# m301-stereo-output.net
KiCad netlist of a schematic drawn in EAGLE
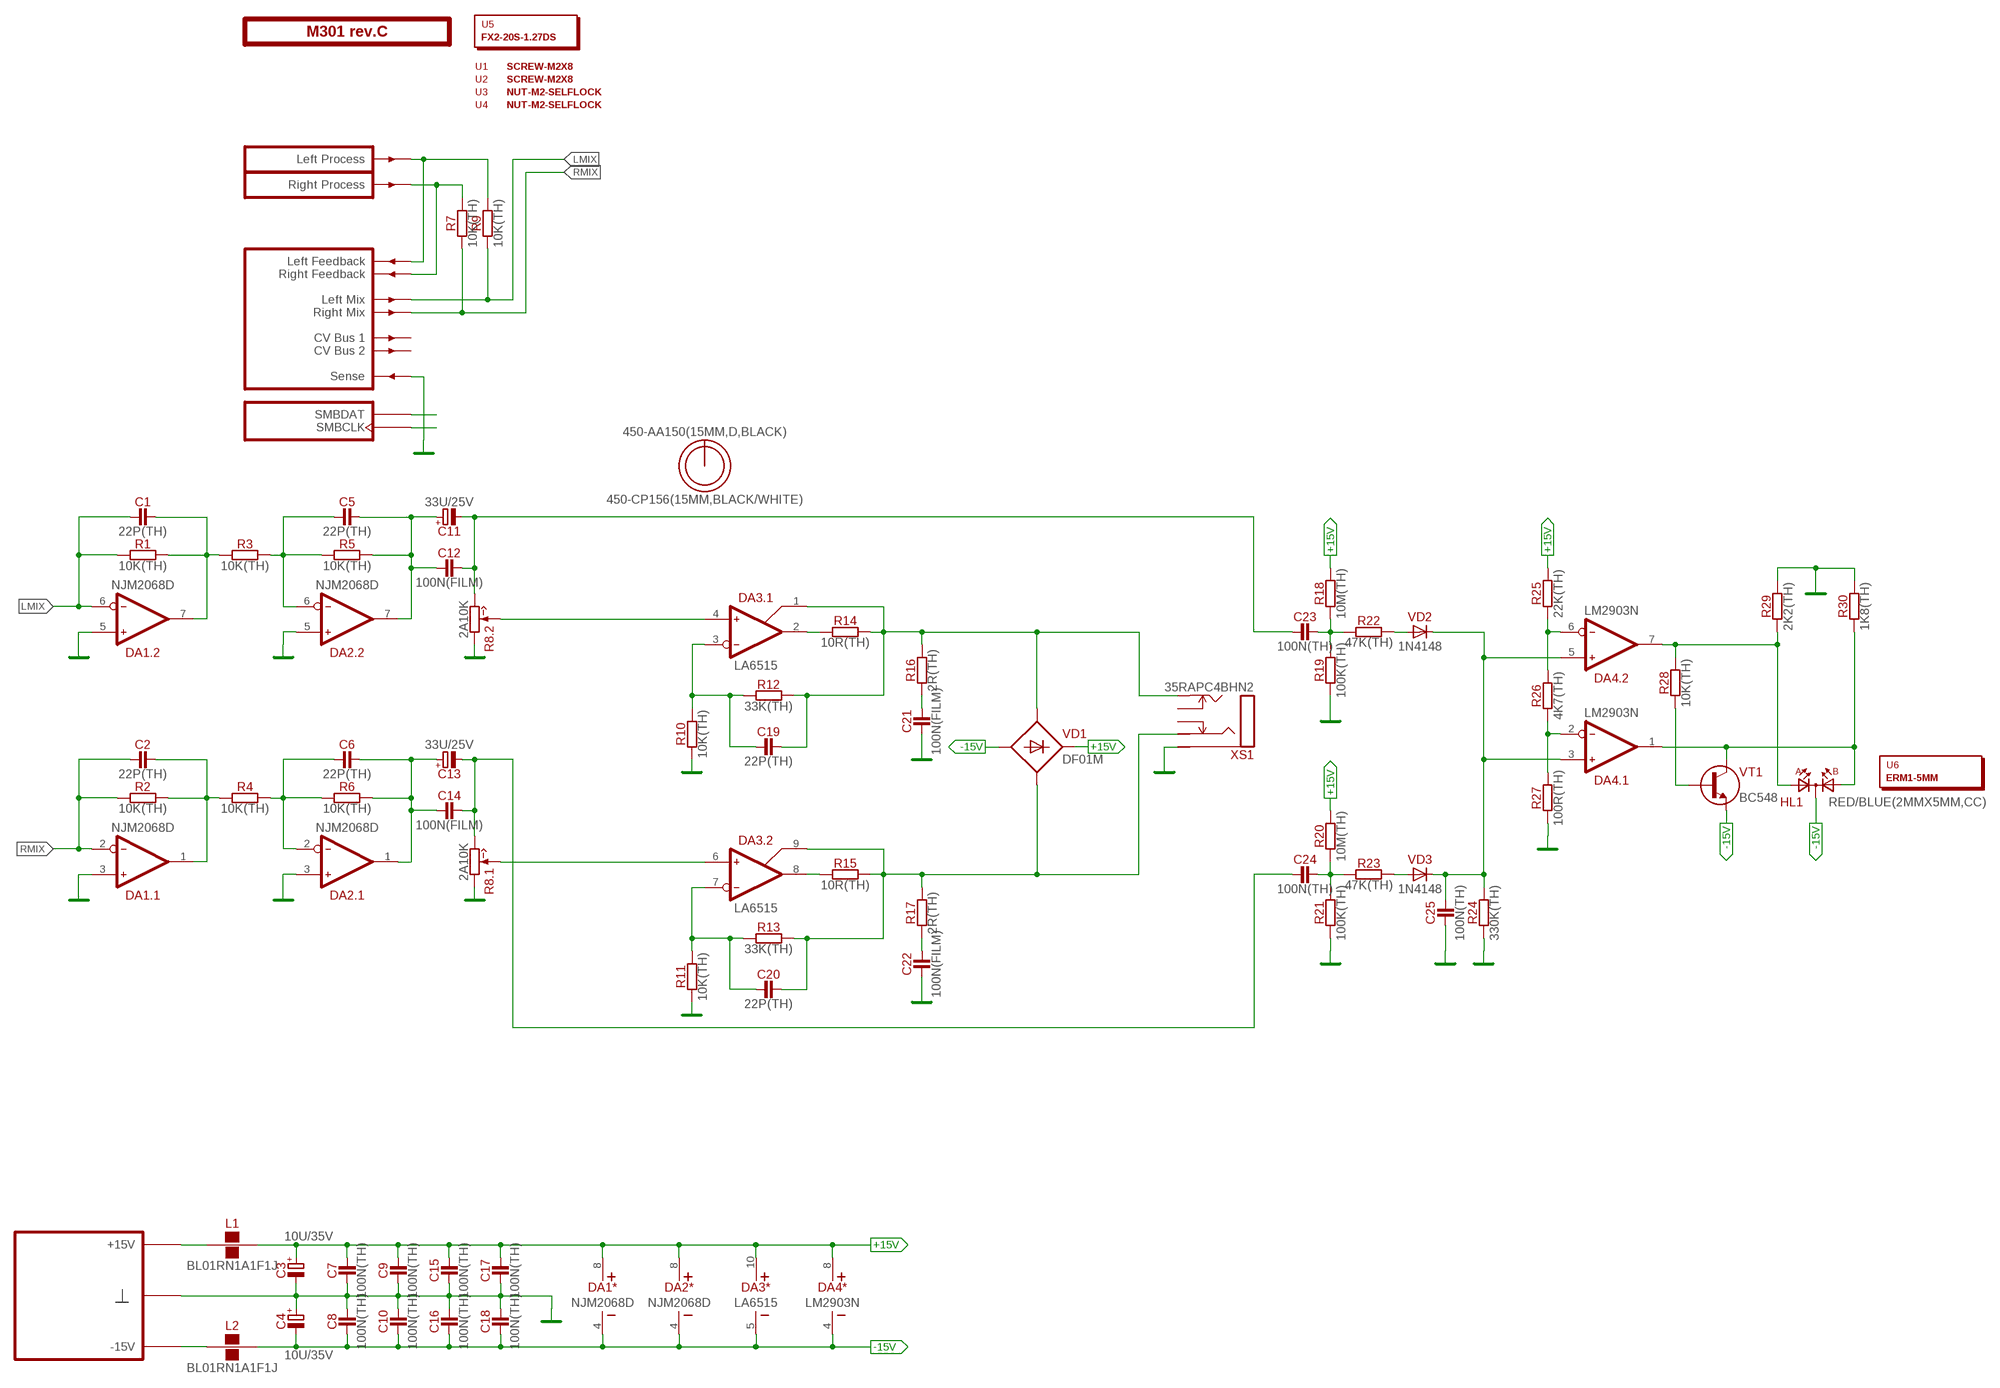
[diagram p0: schematic, sheet 1]

(export (version "E")
  (design (tool "Eeschema 10.0.6"))
  (components
    (comp (ref "C1")
      (value "22P(TH)")
      (footprint "eagle-import:C050-024X044")
      (libsource (lib "eagle-import") (part "?22P(TH)"))
    )
    (comp (ref "C2")
      (value "22P(TH)")
      (footprint "eagle-import:C050-024X044")
      (libsource (lib "eagle-import") (part "?22P(TH)"))
    )
    (comp (ref "C3")
      (value "10U/35V")
      (footprint "eagle-import:E2-5")
      (libsource (lib "eagle-import") (part "?10U/35V"))
    )
    (comp (ref "C4")
      (value "10U/35V")
      (footprint "eagle-import:E2-5")
      (libsource (lib "eagle-import") (part "?10U/35V"))
    )
    (comp (ref "C5")
      (value "22P(TH)")
      (footprint "eagle-import:C050-024X044")
      (libsource (lib "eagle-import") (part "?22P(TH)"))
    )
    (comp (ref "C6")
      (value "22P(TH)")
      (footprint "eagle-import:C050-024X044")
      (libsource (lib "eagle-import") (part "?22P(TH)"))
    )
    (comp (ref "C7")
      (value "100N(TH)")
      (footprint "eagle-import:C050-024X044")
      (libsource (lib "eagle-import") (part "?100N(TH)"))
    )
    (comp (ref "C8")
      (value "100N(TH)")
      (footprint "eagle-import:C050-024X044")
      (libsource (lib "eagle-import") (part "?100N(TH)"))
    )
    (comp (ref "C9")
      (value "100N(TH)")
      (footprint "eagle-import:C050-024X044")
      (libsource (lib "eagle-import") (part "?100N(TH)"))
    )
    (comp (ref "C10")
      (value "100N(TH)")
      (footprint "eagle-import:C050-024X044")
      (libsource (lib "eagle-import") (part "?100N(TH)"))
    )
    (comp (ref "C11")
      (value "33U/25V")
      (footprint "eagle-import:E2,5-7")
      (libsource (lib "eagle-import") (part "?33U/25V"))
    )
    (comp (ref "C12")
      (value "100N(FILM)")
      (footprint "eagle-import:C050-025X075")
      (libsource (lib "eagle-import") (part "?100N(FILM)"))
    )
    (comp (ref "C13")
      (value "33U/25V")
      (footprint "eagle-import:E2,5-7")
      (libsource (lib "eagle-import") (part "?33U/25V"))
    )
    (comp (ref "C14")
      (value "100N(FILM)")
      (footprint "eagle-import:C050-025X075")
      (libsource (lib "eagle-import") (part "?100N(FILM)"))
    )
    (comp (ref "C15")
      (value "100N(TH)")
      (footprint "eagle-import:C050-024X044")
      (libsource (lib "eagle-import") (part "?100N(TH)"))
    )
    (comp (ref "C16")
      (value "100N(TH)")
      (footprint "eagle-import:C050-024X044")
      (libsource (lib "eagle-import") (part "?100N(TH)"))
    )
    (comp (ref "C17")
      (value "100N(TH)")
      (footprint "eagle-import:C050-024X044")
      (libsource (lib "eagle-import") (part "?100N(TH)"))
    )
    (comp (ref "C18")
      (value "100N(TH)")
      (footprint "eagle-import:C050-024X044")
      (libsource (lib "eagle-import") (part "?100N(TH)"))
    )
    (comp (ref "C19")
      (value "22P(TH)")
      (footprint "eagle-import:C050-024X044")
      (libsource (lib "eagle-import") (part "?22P(TH)"))
    )
    (comp (ref "C20")
      (value "22P(TH)")
      (footprint "eagle-import:C050-024X044")
      (libsource (lib "eagle-import") (part "?22P(TH)"))
    )
    (comp (ref "C21")
      (value "100N(FILM)")
      (footprint "eagle-import:C050-025X075")
      (libsource (lib "eagle-import") (part "?100N(FILM)"))
    )
    (comp (ref "C22")
      (value "100N(FILM)")
      (footprint "eagle-import:C050-025X075")
      (libsource (lib "eagle-import") (part "?100N(FILM)"))
    )
    (comp (ref "C23")
      (value "100N(TH)")
      (footprint "eagle-import:C050-024X044")
      (libsource (lib "eagle-import") (part "?100N(TH)"))
    )
    (comp (ref "C24")
      (value "100N(TH)")
      (footprint "eagle-import:C050-024X044")
      (libsource (lib "eagle-import") (part "?100N(TH)"))
    )
    (comp (ref "C25")
      (value "100N(TH)")
      (footprint "eagle-import:C050-024X044")
      (libsource (lib "eagle-import") (part "?100N(TH)"))
    )
    (comp (ref "DA1")
      (value "NJM2068D")
      (footprint "eagle-import:DIP-8")
      (libsource (lib "eagle-import") (part "NJM2068D"))
    )
    (comp (ref "DA2")
      (value "NJM2068D")
      (footprint "eagle-import:DIP-8")
      (libsource (lib "eagle-import") (part "NJM2068D"))
    )
    (comp (ref "DA3")
      (value "LA6515")
      (footprint "eagle-import:SIL10")
      (libsource (lib "eagle-import") (part "LA6515"))
    )
    (comp (ref "DA4")
      (value "LM2903N")
      (footprint "eagle-import:DIP-8")
      (libsource (lib "eagle-import") (part "LM2903N"))
    )
    (comp (ref "HL1")
      (value "RED/BLUE(2MMX5MM,CC)")
      (footprint "eagle-import:LED2X5-3PIN")
      (libsource (lib "eagle-import") (part "?(2MMX5MM,CC)RED/BLUE"))
    )
    (comp (ref "L1")
      (value "BL01RN1A1F1J")
      (footprint "eagle-import:BL01RN1A")
      (libsource (lib "eagle-import") (part "BL01RN1A?1F1J"))
    )
    (comp (ref "L2")
      (value "BL01RN1A1F1J")
      (footprint "eagle-import:BL01RN1A")
      (libsource (lib "eagle-import") (part "BL01RN1A?1F1J"))
    )
    (comp (ref "O1")
      (value "450-AA150(15MM,D,BLACK)")
      (footprint "eagle-import:EMPTY")
      (libsource (lib "eagle-import") (part "450-AA?150(15MM,D,BLACK)"))
    )
    (comp (ref "O2")
      (value "450-CP156(15MM,BLACK/WHITE)")
      (footprint "eagle-import:EMPTY")
      (libsource (lib "eagle-import") (part "450-C?P156(15MM,BLACK/WHITE)"))
    )
    (comp (ref "PCB1")
      (value "M301 rev.C")
      (footprint "eagle-import:ST2-BOARD-50-END")
      (libsource (lib "eagle-import") (part "ST2-BOARD-50-END"))
    )
    (comp (ref "R1")
      (value "10K(TH)")
      (footprint "eagle-import:R-0207_10")
      (libsource (lib "eagle-import") (part "?10K(TH)"))
    )
    (comp (ref "R2")
      (value "10K(TH)")
      (footprint "eagle-import:R-0207_10")
      (libsource (lib "eagle-import") (part "?10K(TH)"))
    )
    (comp (ref "R3")
      (value "10K(TH)")
      (footprint "eagle-import:R-0207_10")
      (libsource (lib "eagle-import") (part "?10K(TH)"))
    )
    (comp (ref "R4")
      (value "10K(TH)")
      (footprint "eagle-import:R-0207_10")
      (libsource (lib "eagle-import") (part "?10K(TH)"))
    )
    (comp (ref "R5")
      (value "10K(TH)")
      (footprint "eagle-import:R-0207_10")
      (libsource (lib "eagle-import") (part "?10K(TH)"))
    )
    (comp (ref "R6")
      (value "10K(TH)")
      (footprint "eagle-import:R-0207_10")
      (libsource (lib "eagle-import") (part "?10K(TH)"))
    )
    (comp (ref "R7")
      (value "10K(TH)")
      (footprint "eagle-import:R-0207_10")
      (libsource (lib "eagle-import") (part "?10K(TH)"))
    )
    (comp (ref "R8")
      (value "2A10K")
      (footprint "eagle-import:RV11-DUAL")
      (libsource (lib "eagle-import") (part "2?A10K"))
    )
    (comp (ref "R9")
      (value "10K(TH)")
      (footprint "eagle-import:R-0207_10")
      (libsource (lib "eagle-import") (part "?10K(TH)"))
    )
    (comp (ref "R10")
      (value "10K(TH)")
      (footprint "eagle-import:R-0207_10")
      (libsource (lib "eagle-import") (part "?10K(TH)"))
    )
    (comp (ref "R11")
      (value "10K(TH)")
      (footprint "eagle-import:R-0207_10")
      (libsource (lib "eagle-import") (part "?10K(TH)"))
    )
    (comp (ref "R12")
      (value "33K(TH)")
      (footprint "eagle-import:R-0207_10")
      (libsource (lib "eagle-import") (part "?33K(TH)"))
    )
    (comp (ref "R13")
      (value "33K(TH)")
      (footprint "eagle-import:R-0207_10")
      (libsource (lib "eagle-import") (part "?33K(TH)"))
    )
    (comp (ref "R14")
      (value "10R(TH)")
      (footprint "eagle-import:R-0207_10")
      (libsource (lib "eagle-import") (part "?10R(TH)"))
    )
    (comp (ref "R15")
      (value "10R(TH)")
      (footprint "eagle-import:R-0207_10")
      (libsource (lib "eagle-import") (part "?10R(TH)"))
    )
    (comp (ref "R16")
      (value "2R(TH)")
      (footprint "eagle-import:R-0207_10")
      (libsource (lib "eagle-import") (part "?2R(TH)"))
    )
    (comp (ref "R17")
      (value "2R(TH)")
      (footprint "eagle-import:R-0207_10")
      (libsource (lib "eagle-import") (part "?2R(TH)"))
    )
    (comp (ref "R18")
      (value "10M(TH)")
      (footprint "eagle-import:R-0207_10")
      (libsource (lib "eagle-import") (part "?10M(TH)"))
    )
    (comp (ref "R19")
      (value "100K(TH)")
      (footprint "eagle-import:R-0207_10")
      (libsource (lib "eagle-import") (part "?100K(TH)"))
    )
    (comp (ref "R20")
      (value "10M(TH)")
      (footprint "eagle-import:R-0207_10")
      (libsource (lib "eagle-import") (part "?10M(TH)"))
    )
    (comp (ref "R21")
      (value "100K(TH)")
      (footprint "eagle-import:R-0207_10")
      (libsource (lib "eagle-import") (part "?100K(TH)"))
    )
    (comp (ref "R22")
      (value "47K(TH)")
      (footprint "eagle-import:R-0207_10")
      (libsource (lib "eagle-import") (part "?47K(TH)"))
    )
    (comp (ref "R23")
      (value "47K(TH)")
      (footprint "eagle-import:R-0207_10")
      (libsource (lib "eagle-import") (part "?47K(TH)"))
    )
    (comp (ref "R24")
      (value "330K(TH)")
      (footprint "eagle-import:R-0207_10")
      (libsource (lib "eagle-import") (part "?330K(TH)"))
    )
    (comp (ref "R25")
      (value "22K(TH)")
      (footprint "eagle-import:R-0207_10")
      (libsource (lib "eagle-import") (part "?22K(TH)"))
    )
    (comp (ref "R26")
      (value "4K7(TH)")
      (footprint "eagle-import:R-0207_10")
      (libsource (lib "eagle-import") (part "?4K7(TH)"))
    )
    (comp (ref "R27")
      (value "100R(TH)")
      (footprint "eagle-import:R-0207_10")
      (libsource (lib "eagle-import") (part "?100R(TH)"))
    )
    (comp (ref "R28")
      (value "10K(TH)")
      (footprint "eagle-import:R-0207_10")
      (libsource (lib "eagle-import") (part "?10K(TH)"))
    )
    (comp (ref "R29")
      (value "2K2(TH)")
      (footprint "eagle-import:R-0207_10")
      (libsource (lib "eagle-import") (part "?2K2(TH)"))
    )
    (comp (ref "R30")
      (value "1K8(TH)")
      (footprint "eagle-import:R-0207_10")
      (libsource (lib "eagle-import") (part "?1K8(TH)"))
    )
    (comp (ref "U1")
      (value "SCREW-M2X8")
      (footprint "eagle-import:EMPTY")
      (libsource (lib "eagle-import") (part "?SCREW-M2X8"))
    )
    (comp (ref "U2")
      (value "SCREW-M2X8")
      (footprint "eagle-import:EMPTY")
      (libsource (lib "eagle-import") (part "?SCREW-M2X8"))
    )
    (comp (ref "U3")
      (value "NUT-M2-SELFLOCK")
      (footprint "eagle-import:EMPTY")
      (libsource (lib "eagle-import") (part "?NUT-M2-SELFLOCK"))
    )
    (comp (ref "U4")
      (value "NUT-M2-SELFLOCK")
      (footprint "eagle-import:EMPTY")
      (libsource (lib "eagle-import") (part "?NUT-M2-SELFLOCK"))
    )
    (comp (ref "U5")
      (value "FX2-20S-1.27DS")
      (footprint "eagle-import:EMPTY")
      (libsource (lib "eagle-import") (part "?FX2-20S-1.27DS"))
    )
    (comp (ref "U6")
      (value "ERM1-5MM")
      (footprint "eagle-import:EMPTY")
      (libsource (lib "eagle-import") (part "?ERM1-5MM"))
    )
    (comp (ref "VD1")
      (value "DF01M")
      (footprint "eagle-import:MDIP-4")
      (libsource (lib "eagle-import") (part "DF?M01"))
    )
    (comp (ref "VD2")
      (value "1N4148")
      (footprint "eagle-import:DO35-7")
      (libsource (lib "eagle-import") (part "?1N4148"))
    )
    (comp (ref "VD3")
      (value "1N4148")
      (footprint "eagle-import:DO35-7")
      (libsource (lib "eagle-import") (part "?1N4148"))
    )
    (comp (ref "VT1")
      (value "BC548")
      (footprint "eagle-import:TO92")
      (libsource (lib "eagle-import") (part "?BC548"))
    )
    (comp (ref "XS1")
      (value "35RAPC4BHN2")
      (footprint "eagle-import:35RAP")
      (libsource (lib "eagle-import") (part "35RAPC4BHN2"))
    )
  )
  (nets
    (net (code "1") (name "+15V") (class "Default")
      (node (ref "C15") (pin "2") (pinfunction "2_2") (pintype "passive"))
      (node (ref "C17") (pin "2") (pinfunction "2_2") (pintype "passive"))
      (node (ref "C3") (pin "+") (pinfunction "+_+") (pintype "passive"))
      (node (ref "C7") (pin "2") (pinfunction "2_2") (pintype "passive"))
      (node (ref "C9") (pin "2") (pinfunction "2_2") (pintype "passive"))
      (node (ref "DA1") (pin "8") (pinfunction "V+_8") (pintype "power_in"))
      (node (ref "DA2") (pin "8") (pinfunction "V+_8") (pintype "power_in"))
      (node (ref "DA3") (pin "10") (pinfunction "V+_10") (pintype "power_in"))
      (node (ref "DA4") (pin "8") (pinfunction "V+_8") (pintype "power_in"))
      (node (ref "L1") (pin "2") (pinfunction "2_2") (pintype "passive"))
      (node (ref "R18") (pin "2") (pinfunction "2_2") (pintype "passive"))
      (node (ref "R20") (pin "2") (pinfunction "2_2") (pintype "passive"))
      (node (ref "R25") (pin "2") (pinfunction "2_2") (pintype "passive"))
      (node (ref "VD1") (pin "3") (pinfunction "C_3") (pintype "passive"))
    )
    (net (code "2") (name "-15V") (class "Default")
      (node (ref "C10") (pin "1") (pinfunction "1_1") (pintype "passive"))
      (node (ref "C16") (pin "1") (pinfunction "1_1") (pintype "passive"))
      (node (ref "C18") (pin "1") (pinfunction "1_1") (pintype "passive"))
      (node (ref "C4") (pin "-") (pinfunction "-_-") (pintype "passive"))
      (node (ref "C8") (pin "1") (pinfunction "1_1") (pintype "passive"))
      (node (ref "DA1") (pin "4") (pinfunction "V-_4") (pintype "power_in"))
      (node (ref "DA2") (pin "4") (pinfunction "V-_4") (pintype "power_in"))
      (node (ref "DA3") (pin "5") (pinfunction "V-_5") (pintype "power_in"))
      (node (ref "DA4") (pin "4") (pinfunction "V-_4") (pintype "power_in"))
      (node (ref "HL1") (pin "K") (pinfunction "K_K") (pintype "passive"))
      (node (ref "L2") (pin "2") (pinfunction "2_2") (pintype "passive"))
      (node (ref "VD1") (pin "4") (pinfunction "A_4") (pintype "passive"))
      (node (ref "VT1") (pin "3") (pinfunction "E_3") (pintype "passive"))
    )
    (net (code "3") (name "GND") (class "Default")
      (node (ref "C10") (pin "2") (pinfunction "2_2") (pintype "passive"))
      (node (ref "C15") (pin "1") (pinfunction "1_1") (pintype "passive"))
      (node (ref "C16") (pin "2") (pinfunction "2_2") (pintype "passive"))
      (node (ref "C17") (pin "1") (pinfunction "1_1") (pintype "passive"))
      (node (ref "C18") (pin "2") (pinfunction "2_2") (pintype "passive"))
      (node (ref "C21") (pin "1") (pinfunction "1_1") (pintype "passive"))
      (node (ref "C22") (pin "1") (pinfunction "1_1") (pintype "passive"))
      (node (ref "C25") (pin "1") (pinfunction "1_1") (pintype "passive"))
      (node (ref "C3") (pin "-") (pinfunction "-_-") (pintype "passive"))
      (node (ref "C4") (pin "+") (pinfunction "+_+") (pintype "passive"))
      (node (ref "C7") (pin "1") (pinfunction "1_1") (pintype "passive"))
      (node (ref "C8") (pin "2") (pinfunction "2_2") (pintype "passive"))
      (node (ref "C9") (pin "1") (pinfunction "1_1") (pintype "passive"))
      (node (ref "DA1") (pin "3") (pinfunction "IN+_3") (pintype "input"))
      (node (ref "DA1") (pin "5") (pinfunction "IN+_5") (pintype "input"))
      (node (ref "DA2") (pin "3") (pinfunction "IN+_3") (pintype "input"))
      (node (ref "DA2") (pin "5") (pinfunction "IN+_5") (pintype "input"))
      (node (ref "PCB1") (pin "B4") (pinfunction "GND_B4") (pintype "bidirectional"))
      (node (ref "PCB1") (pin "B5") (pinfunction "GND_B5") (pintype "bidirectional"))
      (node (ref "PCB1") (pin "B6") (pinfunction "GND_B6") (pintype "bidirectional"))
      (node (ref "PCB1") (pin "B7") (pinfunction "GND_B7") (pintype "bidirectional"))
      (node (ref "PCB1") (pin "B8") (pinfunction "GND_B8") (pintype "bidirectional"))
      (node (ref "PCB1") (pin "BSENSE") (pinfunction "SENSE_BSENSE") (pintype "bidirectional"))
      (node (ref "R10") (pin "1") (pinfunction "1_1") (pintype "passive"))
      (node (ref "R11") (pin "1") (pinfunction "1_1") (pintype "passive"))
      (node (ref "R19") (pin "1") (pinfunction "1_1") (pintype "passive"))
      (node (ref "R21") (pin "1") (pinfunction "1_1") (pintype "passive"))
      (node (ref "R24") (pin "1") (pinfunction "1_1") (pintype "passive"))
      (node (ref "R27") (pin "1") (pinfunction "1_1") (pintype "passive"))
      (node (ref "R29") (pin "2") (pinfunction "2_2") (pintype "passive"))
      (node (ref "R30") (pin "2") (pinfunction "2_2") (pintype "passive"))
      (node (ref "R8") (pin "1") (pinfunction "CCW_1") (pintype "passive"))
      (node (ref "R8") (pin "1'") (pinfunction "CCW_1'") (pintype "passive"))
      (node (ref "XS1") (pin "1") (pinfunction "S_1") (pintype "passive"))
    )
    (net (code "4") (name "LMIX") (class "Default")
      (node (ref "C1") (pin "1") (pinfunction "1_1") (pintype "passive"))
      (node (ref "DA1") (pin "6") (pinfunction "IN-_6") (pintype "input"))
      (node (ref "PCB1") (pin "ALMIX") (pinfunction "LMIX_ALMIX") (pintype "bidirectional"))
      (node (ref "R1") (pin "1") (pinfunction "1_1") (pintype "passive"))
      (node (ref "R9") (pin "1") (pinfunction "1_1") (pintype "passive"))
    )
    (net (code "5") (name "Net-(C21-Pad2)") (class "Default")
      (node (ref "C21") (pin "2") (pinfunction "2_2") (pintype "passive"))
      (node (ref "R16") (pin "1") (pinfunction "1_1") (pintype "passive"))
    )
    (net (code "6") (name "Net-(C22-Pad2)") (class "Default")
      (node (ref "C22") (pin "2") (pinfunction "2_2") (pintype "passive"))
      (node (ref "R17") (pin "1") (pinfunction "1_1") (pintype "passive"))
    )
    (net (code "7") (name "Net-(C23-Pad2)") (class "Default")
      (node (ref "C23") (pin "2") (pinfunction "2_2") (pintype "passive"))
      (node (ref "R18") (pin "1") (pinfunction "1_1") (pintype "passive"))
      (node (ref "R19") (pin "2") (pinfunction "2_2") (pintype "passive"))
      (node (ref "R22") (pin "1") (pinfunction "1_1") (pintype "passive"))
    )
    (net (code "8") (name "Net-(C24-Pad2)") (class "Default")
      (node (ref "C24") (pin "2") (pinfunction "2_2") (pintype "passive"))
      (node (ref "R20") (pin "1") (pinfunction "1_1") (pintype "passive"))
      (node (ref "R21") (pin "2") (pinfunction "2_2") (pintype "passive"))
      (node (ref "R23") (pin "1") (pinfunction "1_1") (pintype "passive"))
    )
    (net (code "9") (name "Net-(DA1B-OUT)") (class "Default")
      (node (ref "C2") (pin "2") (pinfunction "2_2") (pintype "passive"))
      (node (ref "DA1") (pin "1") (pinfunction "OUT_1") (pintype "output"))
      (node (ref "R2") (pin "2") (pinfunction "2_2") (pintype "passive"))
      (node (ref "R4") (pin "1") (pinfunction "1_1") (pintype "passive"))
    )
    (net (code "10") (name "Net-(DA1C-OUT)") (class "Default")
      (node (ref "C1") (pin "2") (pinfunction "2_2") (pintype "passive"))
      (node (ref "DA1") (pin "7") (pinfunction "OUT_7") (pintype "output"))
      (node (ref "R1") (pin "2") (pinfunction "2_2") (pintype "passive"))
      (node (ref "R3") (pin "1") (pinfunction "1_1") (pintype "passive"))
    )
    (net (code "11") (name "Net-(DA2B-IN-)") (class "Default")
      (node (ref "C6") (pin "1") (pinfunction "1_1") (pintype "passive"))
      (node (ref "DA2") (pin "2") (pinfunction "IN-_2") (pintype "input"))
      (node (ref "R4") (pin "2") (pinfunction "2_2") (pintype "passive"))
      (node (ref "R6") (pin "1") (pinfunction "1_1") (pintype "passive"))
    )
    (net (code "12") (name "Net-(DA2B-OUT)") (class "Default")
      (node (ref "C13") (pin "+") (pinfunction "+_+") (pintype "passive"))
      (node (ref "C14") (pin "1") (pinfunction "1_1") (pintype "passive"))
      (node (ref "C6") (pin "2") (pinfunction "2_2") (pintype "passive"))
      (node (ref "DA2") (pin "1") (pinfunction "OUT_1") (pintype "output"))
      (node (ref "R6") (pin "2") (pinfunction "2_2") (pintype "passive"))
    )
    (net (code "13") (name "Net-(DA2C-IN-)") (class "Default")
      (node (ref "C5") (pin "1") (pinfunction "1_1") (pintype "passive"))
      (node (ref "DA2") (pin "6") (pinfunction "IN-_6") (pintype "input"))
      (node (ref "R3") (pin "2") (pinfunction "2_2") (pintype "passive"))
      (node (ref "R5") (pin "1") (pinfunction "1_1") (pintype "passive"))
    )
    (net (code "14") (name "Net-(DA2C-OUT)") (class "Default")
      (node (ref "C11") (pin "+") (pinfunction "+_+") (pintype "passive"))
      (node (ref "C12") (pin "1") (pinfunction "1_1") (pintype "passive"))
      (node (ref "C5") (pin "2") (pinfunction "2_2") (pintype "passive"))
      (node (ref "DA2") (pin "7") (pinfunction "OUT_7") (pintype "output"))
      (node (ref "R5") (pin "2") (pinfunction "2_2") (pintype "passive"))
    )
    (net (code "15") (name "Net-(DA3B-IN+)") (class "Default")
      (node (ref "DA3") (pin "4") (pinfunction "IN+_4") (pintype "input"))
      (node (ref "R8") (pin "2'") (pinfunction "W_2'") (pintype "passive"))
    )
    (net (code "16") (name "Net-(DA3B-IN-)") (class "Default")
      (node (ref "C19") (pin "1") (pinfunction "1_1") (pintype "passive"))
      (node (ref "DA3") (pin "3") (pinfunction "IN-_3") (pintype "input"))
      (node (ref "R10") (pin "2") (pinfunction "2_2") (pintype "passive"))
      (node (ref "R12") (pin "1") (pinfunction "1_1") (pintype "passive"))
    )
    (net (code "17") (name "Net-(DA3B-OUT)") (class "Default")
      (node (ref "DA3") (pin "2") (pinfunction "OUT_2") (pintype "output"))
      (node (ref "R14") (pin "1") (pinfunction "1_1") (pintype "passive"))
    )
    (net (code "18") (name "Net-(DA3B-SENSE)") (class "Default")
      (node (ref "C19") (pin "2") (pinfunction "2_2") (pintype "passive"))
      (node (ref "DA3") (pin "1") (pinfunction "SENSE_1") (pintype "output"))
      (node (ref "R12") (pin "2") (pinfunction "2_2") (pintype "passive"))
      (node (ref "R14") (pin "2") (pinfunction "2_2") (pintype "passive"))
      (node (ref "R16") (pin "2") (pinfunction "2_2") (pintype "passive"))
      (node (ref "VD1") (pin "1") (pinfunction "AC1_1") (pintype "passive"))
      (node (ref "XS1") (pin "2") (pinfunction "T_2") (pintype "passive"))
    )
    (net (code "19") (name "Net-(DA3C-IN+)") (class "Default")
      (node (ref "DA3") (pin "6") (pinfunction "IN+_6") (pintype "input"))
      (node (ref "R8") (pin "2") (pinfunction "W_2") (pintype "passive"))
    )
    (net (code "20") (name "Net-(DA3C-IN-)") (class "Default")
      (node (ref "C20") (pin "1") (pinfunction "1_1") (pintype "passive"))
      (node (ref "DA3") (pin "7") (pinfunction "IN-_7") (pintype "input"))
      (node (ref "R11") (pin "2") (pinfunction "2_2") (pintype "passive"))
      (node (ref "R13") (pin "1") (pinfunction "1_1") (pintype "passive"))
    )
    (net (code "21") (name "Net-(DA3C-OUT)") (class "Default")
      (node (ref "DA3") (pin "8") (pinfunction "OUT_8") (pintype "output"))
      (node (ref "R15") (pin "1") (pinfunction "1_1") (pintype "passive"))
    )
    (net (code "22") (name "Net-(DA3C-SENSE)") (class "Default")
      (node (ref "C20") (pin "2") (pinfunction "2_2") (pintype "passive"))
      (node (ref "DA3") (pin "9") (pinfunction "SENSE_9") (pintype "output"))
      (node (ref "R13") (pin "2") (pinfunction "2_2") (pintype "passive"))
      (node (ref "R15") (pin "2") (pinfunction "2_2") (pintype "passive"))
      (node (ref "R17") (pin "2") (pinfunction "2_2") (pintype "passive"))
      (node (ref "VD1") (pin "2") (pinfunction "AC2_2") (pintype "passive"))
      (node (ref "XS1") (pin "3") (pinfunction "R_3") (pintype "passive"))
    )
    (net (code "23") (name "Net-(DA4B-IN+)") (class "Default")
      (node (ref "C25") (pin "2") (pinfunction "2_2") (pintype "passive"))
      (node (ref "DA4") (pin "3") (pinfunction "IN+_3") (pintype "input"))
      (node (ref "DA4") (pin "5") (pinfunction "IN+_5") (pintype "input"))
      (node (ref "R24") (pin "2") (pinfunction "2_2") (pintype "passive"))
      (node (ref "VD2") (pin "C") (pinfunction "C_C") (pintype "passive"))
      (node (ref "VD3") (pin "C") (pinfunction "C_C") (pintype "passive"))
    )
    (net (code "24") (name "Net-(DA4B-IN-)") (class "Default")
      (node (ref "DA4") (pin "2") (pinfunction "IN-_2") (pintype "input"))
      (node (ref "R26") (pin "1") (pinfunction "1_1") (pintype "passive"))
      (node (ref "R27") (pin "2") (pinfunction "2_2") (pintype "passive"))
    )
    (net (code "25") (name "Net-(DA4B-OUT)") (class "Default")
      (node (ref "DA4") (pin "1") (pinfunction "OUT_1") (pintype "output"))
      (node (ref "HL1") (pin "A2") (pinfunction "A2_A2") (pintype "passive"))
      (node (ref "R30") (pin "1") (pinfunction "1_1") (pintype "passive"))
      (node (ref "VT1") (pin "1") (pinfunction "C_1") (pintype "passive"))
    )
    (net (code "26") (name "Net-(DA4C-IN-)") (class "Default")
      (node (ref "DA4") (pin "6") (pinfunction "IN-_6") (pintype "input"))
      (node (ref "R25") (pin "1") (pinfunction "1_1") (pintype "passive"))
      (node (ref "R26") (pin "2") (pinfunction "2_2") (pintype "passive"))
    )
    (net (code "27") (name "Net-(DA4C-OUT)") (class "Default")
      (node (ref "DA4") (pin "7") (pinfunction "OUT_7") (pintype "output"))
      (node (ref "HL1") (pin "A1") (pinfunction "A1_A1") (pintype "passive"))
      (node (ref "R28") (pin "2") (pinfunction "2_2") (pintype "passive"))
      (node (ref "R29") (pin "1") (pinfunction "1_1") (pintype "passive"))
    )
    (net (code "28") (name "Net-(L1-Pad1)") (class "Default")
      (node (ref "L1") (pin "1") (pinfunction "1_1") (pintype "passive"))
      (node (ref "PCB1") (pin "A+15") (pinfunction "P+15V_A+15") (pintype "bidirectional"))
      (node (ref "PCB1") (pin "B+15") (pinfunction "P+15V_B+15") (pintype "bidirectional"))
    )
    (net (code "29") (name "Net-(L2-Pad1)") (class "Default")
      (node (ref "L2") (pin "1") (pinfunction "1_1") (pintype "passive"))
      (node (ref "PCB1") (pin "A-15") (pinfunction "P-15V_A-15") (pintype "bidirectional"))
      (node (ref "PCB1") (pin "B-15") (pinfunction "P-15V_B-15") (pintype "bidirectional"))
    )
    (net (code "30") (name "Net-(PCB1B-INL)") (class "Default")
      (node (ref "PCB1") (pin "ALFBK") (pinfunction "LFBK_ALFBK") (pintype "bidirectional"))
      (node (ref "PCB1") (pin "BINL") (pinfunction "INL_BINL") (pintype "bidirectional"))
      (node (ref "R9") (pin "2") (pinfunction "2_2") (pintype "passive"))
    )
    (net (code "31") (name "Net-(PCB1C-INR)") (class "Default")
      (node (ref "PCB1") (pin "ARFBK") (pinfunction "RFBK_ARFBK") (pintype "bidirectional"))
      (node (ref "PCB1") (pin "BINR") (pinfunction "INR_BINR") (pintype "bidirectional"))
      (node (ref "R7") (pin "2") (pinfunction "2_2") (pintype "passive"))
    )
    (net (code "32") (name "Net-(R8A-CW)") (class "Default")
      (node (ref "C13") (pin "-") (pinfunction "-_-") (pintype "passive"))
      (node (ref "C14") (pin "2") (pinfunction "2_2") (pintype "passive"))
      (node (ref "C24") (pin "1") (pinfunction "1_1") (pintype "passive"))
      (node (ref "R8") (pin "3") (pinfunction "CW_3") (pintype "passive"))
    )
    (net (code "33") (name "Net-(R8B-CW)") (class "Default")
      (node (ref "C11") (pin "-") (pinfunction "-_-") (pintype "passive"))
      (node (ref "C12") (pin "2") (pinfunction "2_2") (pintype "passive"))
      (node (ref "C23") (pin "1") (pinfunction "1_1") (pintype "passive"))
      (node (ref "R8") (pin "3'") (pinfunction "CW_3'") (pintype "passive"))
    )
    (net (code "34") (name "Net-(R22-Pad2)") (class "Default")
      (node (ref "R22") (pin "2") (pinfunction "2_2") (pintype "passive"))
      (node (ref "VD2") (pin "A") (pinfunction "A_A") (pintype "passive"))
    )
    (net (code "35") (name "Net-(R23-Pad2)") (class "Default")
      (node (ref "R23") (pin "2") (pinfunction "2_2") (pintype "passive"))
      (node (ref "VD3") (pin "A") (pinfunction "A_A") (pintype "passive"))
    )
    (net (code "36") (name "Net-(VT1-B)") (class "Default")
      (node (ref "R28") (pin "1") (pinfunction "1_1") (pintype "passive"))
      (node (ref "VT1") (pin "2") (pinfunction "B_2") (pintype "passive"))
    )
    (net (code "37") (name "RMIX") (class "Default")
      (node (ref "C2") (pin "1") (pinfunction "1_1") (pintype "passive"))
      (node (ref "DA1") (pin "2") (pinfunction "IN-_2") (pintype "input"))
      (node (ref "PCB1") (pin "ARMIX") (pinfunction "RMIX_ARMIX") (pintype "bidirectional"))
      (node (ref "R2") (pin "1") (pinfunction "1_1") (pintype "passive"))
      (node (ref "R7") (pin "1") (pinfunction "1_1") (pintype "passive"))
    )
    (net (code "38") (name "unconnected-(PCB1D-CV1-PadACV1)") (class "Default")
      (node (ref "PCB1") (pin "ACV1") (pinfunction "CV1_ACV1") (pintype "bidirectional"))
    )
    (net (code "39") (name "unconnected-(PCB1D-CV2-PadACV2)") (class "Default")
      (node (ref "PCB1") (pin "ACV2") (pinfunction "CV2_ACV2") (pintype "bidirectional"))
    )
    (net (code "40") (name "unconnected-(PCB1E-SMBCLK-PadASMBCLK)") (class "Default")
      (node (ref "PCB1") (pin "ASMBCLK") (pinfunction "SMBCLK_ASMBCLK") (pintype "bidirectional"))
    )
    (net (code "41") (name "unconnected-(PCB1E-SMBDAT-PadASMBDAT)") (class "Default")
      (node (ref "PCB1") (pin "ASMBDAT") (pinfunction "SMBDAT_ASMBDAT") (pintype "bidirectional"))
    )
    (net (code "42") (name "unconnected-(XS1-RN-Pad11)") (class "Default")
      (node (ref "XS1") (pin "11") (pinfunction "RN_11") (pintype "passive"))
    )
    (net (code "43") (name "unconnected-(XS1-TN-Pad10)") (class "Default")
      (node (ref "XS1") (pin "10") (pinfunction "TN_10") (pintype "passive"))
    )
  )
)
